# LedDriver.net
KiCad netlist of a schematic drawn in Altium Designer
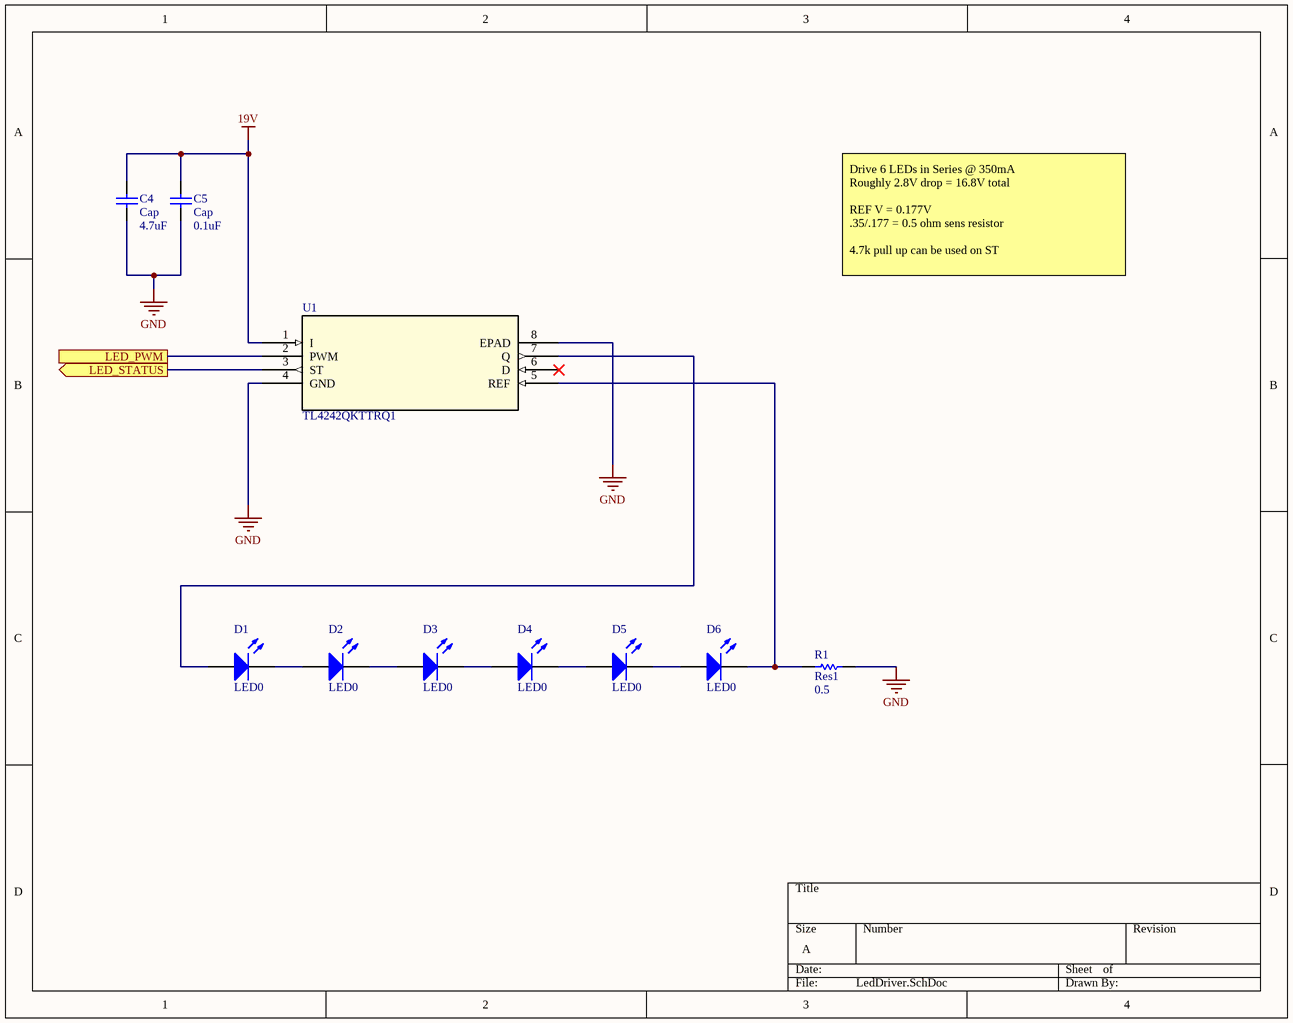
[diagram p0: LedDriver.SchDoc]

(export (version "E")
  (design (tool "Eeschema 10.0.6"))
  (components
    (comp (ref "C4")
      (value "Cap")
      (footprint "RAD-0.3")
      (description "Capacitor")
      (fields (field (name "ALTIUM_VALUE") "4.7uF") (field (name "PUBLISHER") "Altium Limited"))
      (libsource (lib "Miscellaneous Devices") (part "Cap"))
    )
    (comp (ref "C5")
      (value "Cap")
      (footprint "RAD-0.3")
      (description "Capacitor")
      (fields (field (name "ALTIUM_VALUE") "0.1uF") (field (name "PUBLISHER") "Altium Limited"))
      (libsource (lib "Miscellaneous Devices") (part "Cap"))
    )
    (comp (ref "D1")
      (value "LED0")
      (footprint "LED-0")
      (description "Typical INFRARED GaAs LED")
      (fields (field (name "PUBLISHER") "Altium Limited"))
      (libsource (lib "Miscellaneous Devices") (part "LED0"))
    )
    (comp (ref "D2")
      (value "LED0")
      (footprint "LED-0")
      (description "Typical INFRARED GaAs LED")
      (fields (field (name "PUBLISHER") "Altium Limited"))
      (libsource (lib "Miscellaneous Devices") (part "LED0"))
    )
    (comp (ref "D3")
      (value "LED0")
      (footprint "LED-0")
      (description "Typical INFRARED GaAs LED")
      (fields (field (name "PUBLISHER") "Altium Limited"))
      (libsource (lib "Miscellaneous Devices") (part "LED0"))
    )
    (comp (ref "D4")
      (value "LED0")
      (footprint "LED-0")
      (description "Typical INFRARED GaAs LED")
      (fields (field (name "PUBLISHER") "Altium Limited"))
      (libsource (lib "Miscellaneous Devices") (part "LED0"))
    )
    (comp (ref "D5")
      (value "LED0")
      (footprint "LED-0")
      (description "Typical INFRARED GaAs LED")
      (fields (field (name "PUBLISHER") "Altium Limited"))
      (libsource (lib "Miscellaneous Devices") (part "LED0"))
    )
    (comp (ref "D6")
      (value "LED0")
      (footprint "LED-0")
      (description "Typical INFRARED GaAs LED")
      (fields (field (name "PUBLISHER") "Altium Limited"))
      (libsource (lib "Miscellaneous Devices") (part "LED0"))
    )
    (comp (ref "R1")
      (value "Res1")
      (footprint "AXIAL-0.3")
      (description "Resistor")
      (fields (field (name "ALTIUM_VALUE") "0.5") (field (name "PUBLISHER") "Altium Limited"))
      (libsource (lib "Miscellaneous Devices") (part "Res1"))
    )
    (comp (ref "U1")
      (value "TL4242QKTTRQ1")
      (footprint "KTT7")
      (description "Automotive Catalog Adjustable LED Driver")
      (fields
        (field (name "GENERIC_PART_NUMBER") "TL4242-Q1")
        (field (name "MANUFACTURER") "Texas Instruments")
        (field (name "COPYRIGHT") "Copyright (C) 2018 Accelerated Designs. All rights reserved")
      )
      (libsource (lib "2020-09-21_00-39-54") (part "TL4242QKTTRQ1"))
    )
  )
  (nets
    (net (code "1") (name "/LED_PWM") (class "Default")
      (node (ref "U1") (pin "2") (pinfunction "PWM_2") (pintype "power_in"))
    )
    (net (code "2") (name "/LED_STATUS") (class "Default")
      (node (ref "U1") (pin "3") (pinfunction "ST_3") (pintype "output"))
    )
    (net (code "3") (name "19V") (class "Default")
      (node (ref "C4") (pin "2") (pinfunction "2_2") (pintype "passive"))
      (node (ref "C5") (pin "2") (pinfunction "2_2") (pintype "passive"))
      (node (ref "U1") (pin "1") (pinfunction "I_1") (pintype "input"))
    )
    (net (code "4") (name "GND") (class "Default")
      (node (ref "C4") (pin "1") (pinfunction "1_1") (pintype "passive"))
      (node (ref "C5") (pin "1") (pinfunction "1_1") (pintype "passive"))
      (node (ref "R1") (pin "2") (pinfunction "2_2") (pintype "passive"))
      (node (ref "U1") (pin "4") (pinfunction "GND_4") (pintype "power_in"))
      (node (ref "U1") (pin "8") (pinfunction "EPAD_8") (pintype "passive"))
    )
    (net (code "5") (name "Net-(D1-A)") (class "Default")
      (node (ref "D1") (pin "1") (pinfunction "A_1") (pintype "passive"))
      (node (ref "U1") (pin "7") (pinfunction "Q_7") (pintype "output"))
    )
    (net (code "6") (name "Net-(D1-K)") (class "Default")
      (node (ref "D1") (pin "2") (pinfunction "K_2") (pintype "passive"))
      (node (ref "D2") (pin "1") (pinfunction "A_1") (pintype "passive"))
    )
    (net (code "7") (name "Net-(D2-K)") (class "Default")
      (node (ref "D2") (pin "2") (pinfunction "K_2") (pintype "passive"))
      (node (ref "D3") (pin "1") (pinfunction "A_1") (pintype "passive"))
    )
    (net (code "8") (name "Net-(D3-K)") (class "Default")
      (node (ref "D3") (pin "2") (pinfunction "K_2") (pintype "passive"))
      (node (ref "D4") (pin "1") (pinfunction "A_1") (pintype "passive"))
    )
    (net (code "9") (name "Net-(D4-K)") (class "Default")
      (node (ref "D4") (pin "2") (pinfunction "K_2") (pintype "passive"))
      (node (ref "D5") (pin "1") (pinfunction "A_1") (pintype "passive"))
    )
    (net (code "10") (name "Net-(D5-K)") (class "Default")
      (node (ref "D5") (pin "2") (pinfunction "K_2") (pintype "passive"))
      (node (ref "D6") (pin "1") (pinfunction "A_1") (pintype "passive"))
    )
    (net (code "11") (name "Net-(D6-K)") (class "Default")
      (node (ref "D6") (pin "2") (pinfunction "K_2") (pintype "passive"))
      (node (ref "R1") (pin "1") (pinfunction "1_1") (pintype "passive"))
      (node (ref "U1") (pin "5") (pinfunction "REF_5") (pintype "input"))
    )
    (net (code "12") (name "unconnected-(U1-D-Pad6)") (class "Default")
      (node (ref "U1") (pin "6") (pinfunction "D_6") (pintype "input+no_connect"))
    )
  )
)
